# Motor_and_Power_IO.net
KiCad netlist of a schematic drawn in Altium Designer
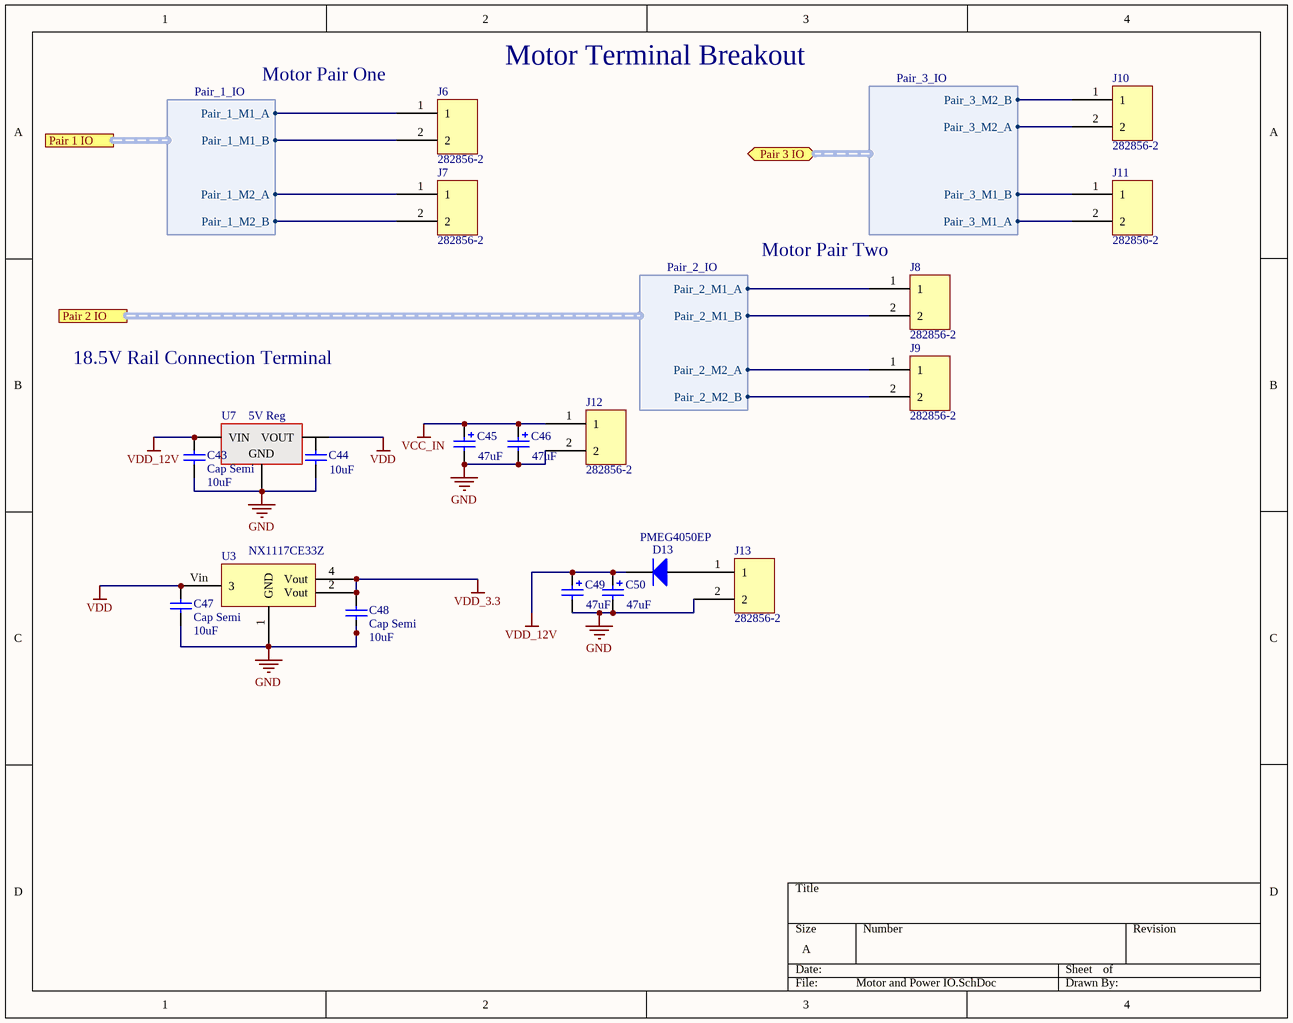
[diagram p0: Motor and Power IO.SchDoc]

(export (version "E")
  (design (tool "Eeschema 10.0.6"))
  (components
    (comp (ref "C43")
      (value "Cap Semi")
      (footprint "C1206")
      (description "Capacitor (Semiconductor SIM Model)")
      (fields (field (name "ALTIUM_VALUE") "10uF") (field (name "PUBLISHER") "Altium Limited"))
      (libsource (lib "Miscellaneous Devices") (part "Cap Semi"))
    )
    (comp (ref "C44")
      (value "10uF")
      (footprint "C1206")
      (description "Capacitor (Semiconductor SIM Model)")
      (fields (field (name "Comment") "Cap Semi") (field (name "PUBLISHER") "Altium Limited"))
      (libsource (lib "Miscellaneous Devices") (part "Cap Semi"))
    )
    (comp (ref "C45")
      (value "47uF")
      (footprint "CAPPR2-5x6.8")
      (description "Polarized Capacitor (Axial)")
      (fields (field (name "Comment") "Cap Pol2") (field (name "PUBLISHER") "Altium Limited"))
      (libsource (lib "Miscellaneous Devices") (part "Cap Pol2"))
    )
    (comp (ref "C46")
      (value "47uF")
      (footprint "CAPPR2-5x6.8")
      (description "Polarized Capacitor (Axial)")
      (fields (field (name "Comment") "Cap Pol2") (field (name "PUBLISHER") "Altium Limited"))
      (libsource (lib "Miscellaneous Devices") (part "Cap Pol2"))
    )
    (comp (ref "C47")
      (value "Cap Semi")
      (footprint "C1206")
      (description "Capacitor (Semiconductor SIM Model)")
      (fields (field (name "ALTIUM_VALUE") "10uF") (field (name "PUBLISHER") "Altium Limited"))
      (libsource (lib "Miscellaneous Devices") (part "Cap Semi"))
    )
    (comp (ref "C48")
      (value "Cap Semi")
      (footprint "C1206")
      (description "Capacitor (Semiconductor SIM Model)")
      (fields (field (name "ALTIUM_VALUE") "10uF") (field (name "PUBLISHER") "Altium Limited"))
      (libsource (lib "Miscellaneous Devices") (part "Cap Semi"))
    )
    (comp (ref "C49")
      (value "47uF")
      (footprint "CAPPR2-5x6.8")
      (description "Polarized Capacitor (Axial)")
      (fields (field (name "Comment") "Cap Pol2") (field (name "PUBLISHER") "Altium Limited"))
      (libsource (lib "Miscellaneous Devices") (part "Cap Pol2"))
    )
    (comp (ref "C50")
      (value "47uF")
      (footprint "CAPPR2-5x6.8")
      (description "Polarized Capacitor (Axial)")
      (fields (field (name "Comment") "Cap Pol2") (field (name "PUBLISHER") "Altium Limited"))
      (libsource (lib "Miscellaneous Devices") (part "Cap Pol2"))
    )
    (comp (ref "D13")
      (value "PMEG4050EP")
      (footprint "PMEG4050EP")
      (description "Default Diode")
      (fields (field (name "PUBLISHER") "Altium Limited"))
      (libsource (lib "Miscellaneous Devices") (part "Diode"))
    )
    (comp (ref "J6")
      (value "282856-2")
      (footprint "282856-2")
      (description "Two pole screw terminal")
      (libsource (lib "Thruster Shield Part Library") (part "282856-2"))
    )
    (comp (ref "J7")
      (value "282856-2")
      (footprint "282856-2")
      (description "Two pole screw terminal")
      (libsource (lib "Thruster Shield Part Library") (part "282856-2"))
    )
    (comp (ref "J8")
      (value "282856-2")
      (footprint "282856-2")
      (description "Two pole screw terminal")
      (libsource (lib "Thruster Shield Part Library") (part "282856-2"))
    )
    (comp (ref "J9")
      (value "282856-2")
      (footprint "282856-2")
      (description "Two pole screw terminal")
      (libsource (lib "Thruster Shield Part Library") (part "282856-2"))
    )
    (comp (ref "J10")
      (value "282856-2")
      (footprint "282856-2")
      (description "Two pole screw terminal")
      (libsource (lib "Thruster Shield Part Library") (part "282856-2"))
    )
    (comp (ref "J11")
      (value "282856-2")
      (footprint "282856-2")
      (description "Two pole screw terminal")
      (libsource (lib "Thruster Shield Part Library") (part "282856-2"))
    )
    (comp (ref "J12")
      (value "282856-2")
      (footprint "282856-2")
      (description "Two pole screw terminal")
      (libsource (lib "Thruster Shield Part Library") (part "282856-2"))
    )
    (comp (ref "J13")
      (value "282856-2")
      (footprint "282856-2")
      (description "Two pole screw terminal")
      (libsource (lib "Thruster Shield Part Library") (part "282856-2"))
    )
    (comp (ref "U3")
      (value "NX1117CE33Z")
      (footprint "NX1117CE33Z")
      (description "3.3v Linear Regulator")
      (libsource (lib "AHD Part Library") (part "NX1117CE33Z"))
    )
    (comp (ref "U7")
      (value "5V Reg")
      (footprint "DPAK-3")
      (description "Voltage regulator")
      (fields (field (name "PUBLISHER") "Altium Limited"))
      (libsource (lib "Rascal") (part "VOLT REG"))
    )
  )
  (nets
    (net (code "4") (name "/Pair_1_M1_A") (class "Default")
      (node (ref "J6") (pin "1") (pinfunction "1_1") (pintype "passive"))
    )
    (net (code "5") (name "/Pair_1_M1_B") (class "Default")
      (node (ref "J6") (pin "2") (pinfunction "2_2") (pintype "passive"))
    )
    (net (code "6") (name "/Pair_1_M2_A") (class "Default")
      (node (ref "J7") (pin "1") (pinfunction "1_1") (pintype "passive"))
    )
    (net (code "7") (name "/Pair_1_M2_B") (class "Default")
      (node (ref "J7") (pin "2") (pinfunction "2_2") (pintype "passive"))
    )
    (net (code "8") (name "/Pair_2_M1_A") (class "Default")
      (node (ref "J8") (pin "1") (pinfunction "1_1") (pintype "passive"))
    )
    (net (code "9") (name "/Pair_2_M1_B") (class "Default")
      (node (ref "J8") (pin "2") (pinfunction "2_2") (pintype "passive"))
    )
    (net (code "10") (name "/Pair_2_M2_A") (class "Default")
      (node (ref "J9") (pin "1") (pinfunction "1_1") (pintype "passive"))
    )
    (net (code "11") (name "/Pair_2_M2_B") (class "Default")
      (node (ref "J9") (pin "2") (pinfunction "2_2") (pintype "passive"))
    )
    (net (code "12") (name "/Pair_3_M1_A") (class "Default")
      (node (ref "J11") (pin "2") (pinfunction "2_2") (pintype "passive"))
    )
    (net (code "13") (name "/Pair_3_M1_B") (class "Default")
      (node (ref "J11") (pin "1") (pinfunction "1_1") (pintype "passive"))
    )
    (net (code "14") (name "/Pair_3_M2_A") (class "Default")
      (node (ref "J10") (pin "2") (pinfunction "2_2") (pintype "passive"))
    )
    (net (code "15") (name "/Pair_3_M2_B") (class "Default")
      (node (ref "J10") (pin "1") (pinfunction "1_1") (pintype "passive"))
    )
    (net (code "19") (name "GND") (class "Default")
      (node (ref "C43") (pin "1") (pinfunction "1_1") (pintype "passive"))
      (node (ref "C44") (pin "1") (pinfunction "1_1") (pintype "passive"))
      (node (ref "C45") (pin "2") (pinfunction "2_2") (pintype "passive"))
      (node (ref "C46") (pin "2") (pinfunction "2_2") (pintype "passive"))
      (node (ref "C47") (pin "1") (pinfunction "1_1") (pintype "passive"))
      (node (ref "C48") (pin "1") (pinfunction "1_1") (pintype "passive"))
      (node (ref "C49") (pin "2") (pinfunction "2_2") (pintype "passive"))
      (node (ref "C50") (pin "2") (pinfunction "2_2") (pintype "passive"))
      (node (ref "J12") (pin "2") (pinfunction "2_2") (pintype "passive"))
      (node (ref "J13") (pin "2") (pinfunction "2_2") (pintype "passive"))
      (node (ref "U3") (pin "1") (pinfunction "GND_1") (pintype "passive"))
      (node (ref "U7") (pin "2") (pinfunction "GND_2") (pintype "passive"))
    )
    (net (code "20") (name "Net-(D13-K)") (class "Default")
      (node (ref "D13") (pin "2") (pinfunction "K_2") (pintype "passive"))
      (node (ref "J13") (pin "1") (pinfunction "1_1") (pintype "passive"))
    )
    (net (code "21") (name "VCC_IN") (class "Default")
      (node (ref "C45") (pin "1") (pinfunction "1_1") (pintype "passive"))
      (node (ref "C46") (pin "1") (pinfunction "1_1") (pintype "passive"))
      (node (ref "J12") (pin "1") (pinfunction "1_1") (pintype "passive"))
    )
    (net (code "22") (name "VDD") (class "Default")
      (node (ref "C47") (pin "2") (pinfunction "2_2") (pintype "passive"))
      (node (ref "U3") (pin "Vin") (pinfunction "3_Vin") (pintype "passive"))
      (node (ref "U7") (pin "3") (pinfunction "VOUT_3") (pintype "passive"))
    )
    (net (code "23") (name "VDD_3.3") (class "Default")
      (node (ref "C48") (pin "2") (pinfunction "2_2") (pintype "passive"))
      (node (ref "U3") (pin "2") (pinfunction "Vout_2") (pintype "passive"))
      (node (ref "U3") (pin "4") (pinfunction "Vout_4") (pintype "passive"))
    )
    (net (code "24") (name "VDD_12V") (class "Default")
      (node (ref "C43") (pin "2") (pinfunction "2_2") (pintype "passive"))
      (node (ref "C49") (pin "1") (pinfunction "1_1") (pintype "passive"))
      (node (ref "C50") (pin "1") (pinfunction "1_1") (pintype "passive"))
      (node (ref "D13") (pin "1") (pinfunction "A_1") (pintype "passive"))
      (node (ref "U7") (pin "1") (pinfunction "VIN_1") (pintype "passive"))
    )
    (net (code "25") (name "unconnected-(C44-Pad2)") (class "Default")
      (node (ref "C44") (pin "2") (pinfunction "2_2") (pintype "passive"))
    )
  )
)
